# Wave_Fold_Osc_MAIN_V2_1.net
KiCad netlist of a schematic drawn in EAGLE
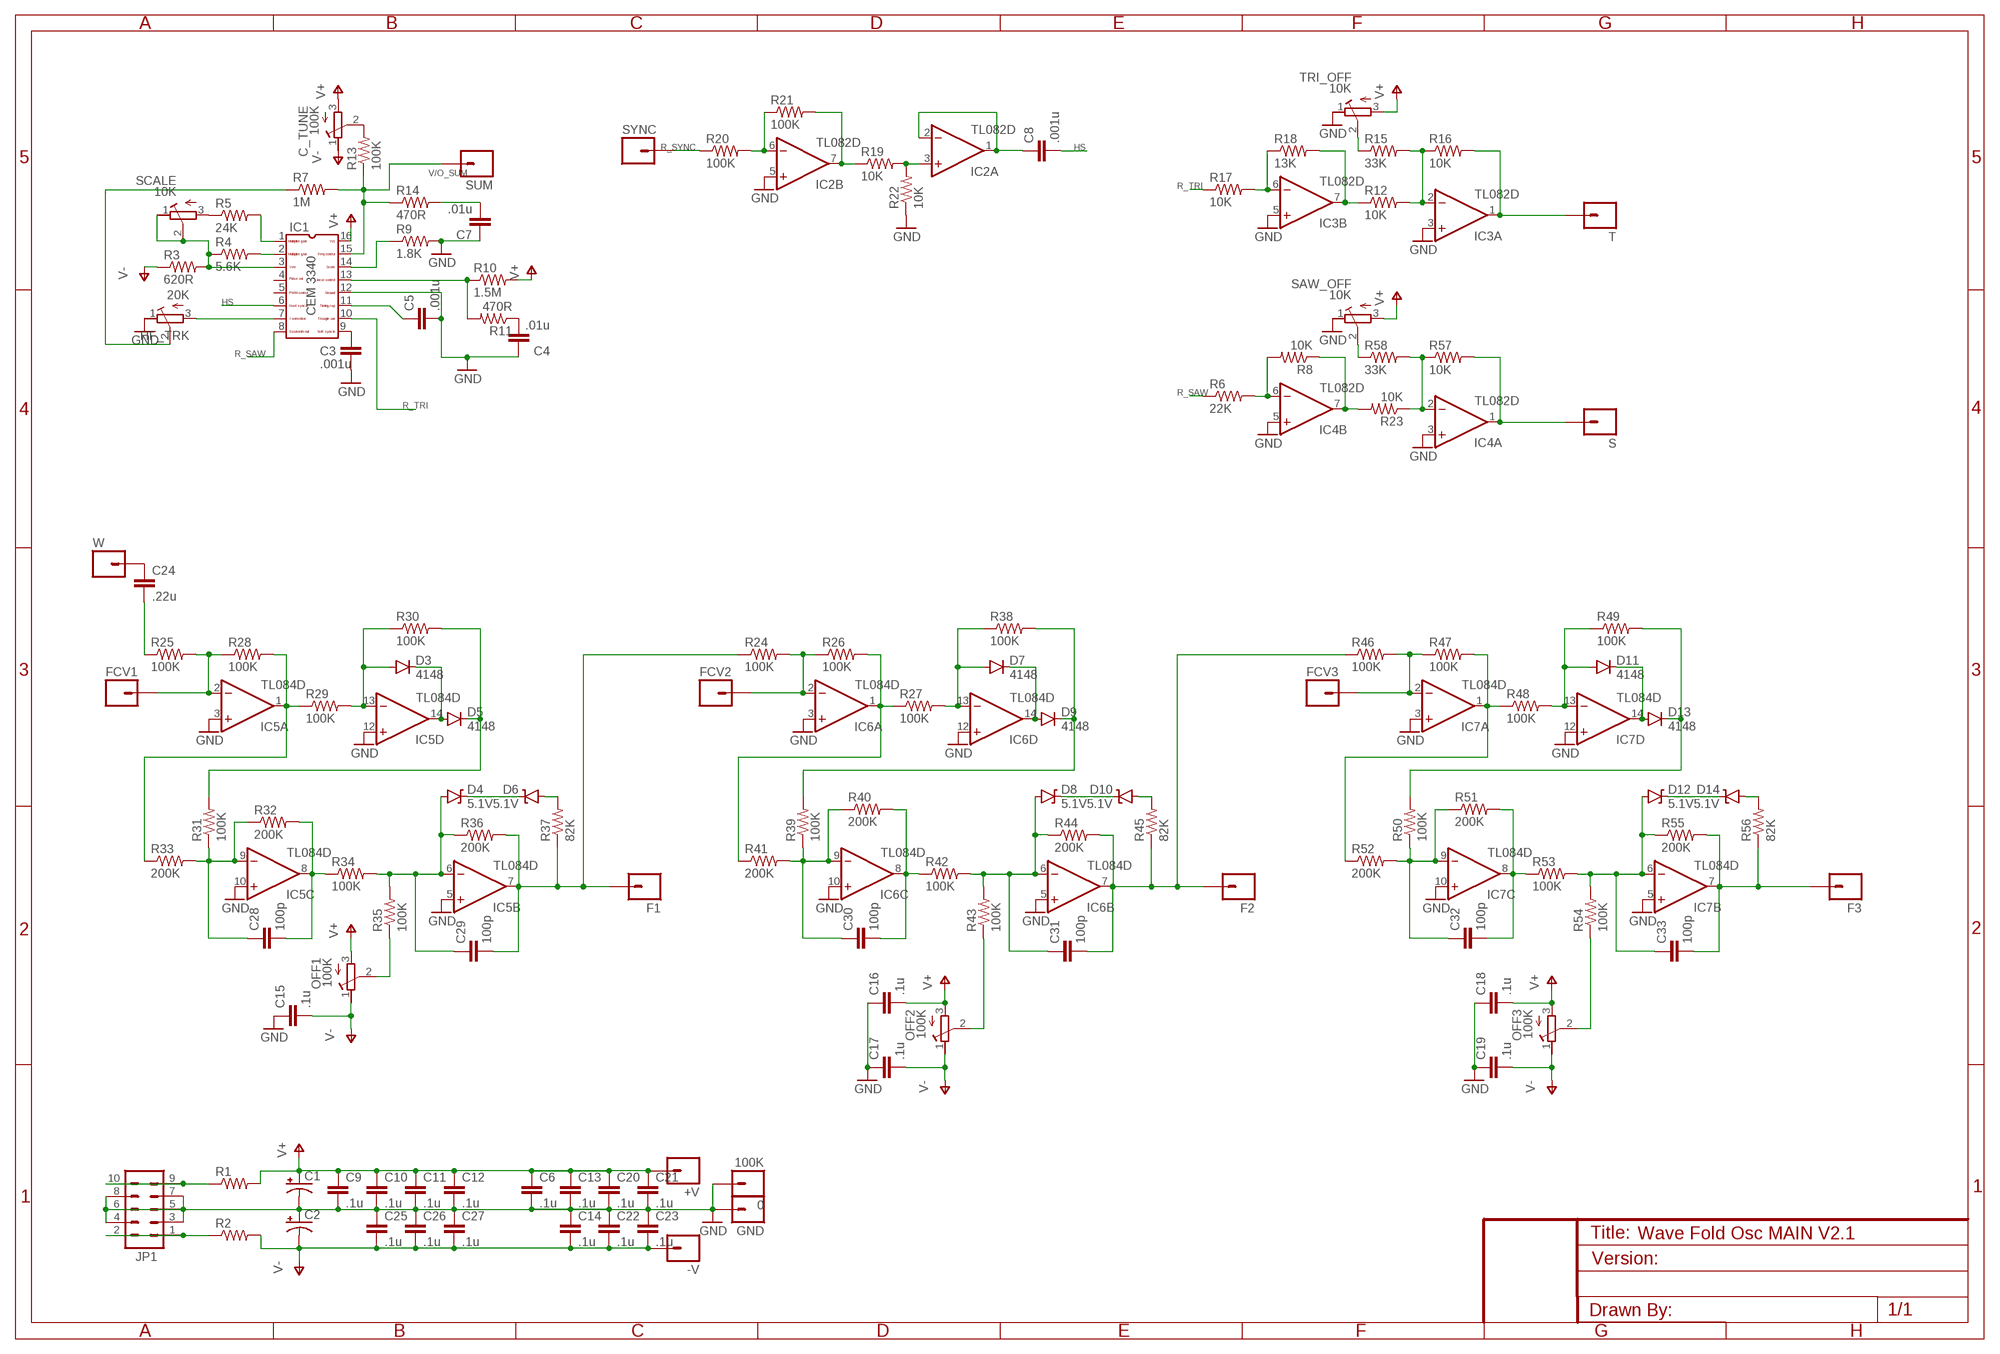
[diagram p0: schematic, sheet 1]

(export (version "E")
  (design (tool "Eeschema 10.0.6"))
  (components
    (comp (ref "+V")
      (value "M01PTH")
      (footprint "eagle-import:1X01")
      (libsource (lib "eagle-import") (part "M01PTH"))
    )
    (comp (ref "-V")
      (value "M01PTH")
      (footprint "eagle-import:1X01")
      (libsource (lib "eagle-import") (part "M01PTH"))
    )
    (comp (ref "0")
      (value "100K")
      (footprint "eagle-import:1X01")
      (libsource (lib "eagle-import") (part "M01PTH"))
    )
    (comp (ref "C1")
      (value "CAP_POLC")
      (footprint "eagle-import:PANASONIC_C")
      (libsource (lib "eagle-import") (part "CAP_POLC"))
    )
    (comp (ref "C2")
      (value "CAP_POLC")
      (footprint "eagle-import:PANASONIC_C")
      (libsource (lib "eagle-import") (part "CAP_POLC"))
    )
    (comp (ref "C3")
      (value ".001u")
      (footprint "eagle-import:0805")
      (libsource (lib "eagle-import") (part "CAP0805"))
    )
    (comp (ref "C4")
      (value ".01u")
      (footprint "eagle-import:0805")
      (libsource (lib "eagle-import") (part "CAP0805"))
    )
    (comp (ref "C5")
      (value ".001u")
      (footprint "eagle-import:C5B2.5")
      (libsource (lib "eagle-import") (part "C5/2.5"))
    )
    (comp (ref "C6")
      (value ".1u")
      (footprint "eagle-import:0805@1")
      (libsource (lib "eagle-import") (part "SparkFun-Passives_CAP0805"))
    )
    (comp (ref "C7")
      (value ".01u")
      (footprint "eagle-import:0805")
      (libsource (lib "eagle-import") (part "CAP0805"))
    )
    (comp (ref "C8")
      (value ".001u")
      (footprint "eagle-import:0805")
      (libsource (lib "eagle-import") (part "CAP0805"))
    )
    (comp (ref "C9")
      (value ".1u")
      (footprint "eagle-import:0805@1")
      (libsource (lib "eagle-import") (part "SparkFun-Passives_CAP0805"))
    )
    (comp (ref "C10")
      (value ".1u")
      (footprint "eagle-import:0805@1")
      (libsource (lib "eagle-import") (part "SparkFun-Passives_CAP0805"))
    )
    (comp (ref "C11")
      (value ".1u")
      (footprint "eagle-import:0805@1")
      (libsource (lib "eagle-import") (part "SparkFun-Passives_CAP0805"))
    )
    (comp (ref "C12")
      (value ".1u")
      (footprint "eagle-import:0805@1")
      (libsource (lib "eagle-import") (part "SparkFun-Passives_CAP0805"))
    )
    (comp (ref "C13")
      (value ".1u")
      (footprint "eagle-import:0805@1")
      (libsource (lib "eagle-import") (part "SparkFun-Passives_CAP0805"))
    )
    (comp (ref "C14")
      (value ".1u")
      (footprint "eagle-import:0805@1")
      (libsource (lib "eagle-import") (part "SparkFun-Passives_CAP0805"))
    )
    (comp (ref "C15")
      (value ".1u")
      (footprint "eagle-import:0805")
      (libsource (lib "eagle-import") (part "CAP0805"))
    )
    (comp (ref "C16")
      (value ".1u")
      (footprint "eagle-import:0805")
      (libsource (lib "eagle-import") (part "CAP0805"))
    )
    (comp (ref "C17")
      (value ".1u")
      (footprint "eagle-import:0805")
      (libsource (lib "eagle-import") (part "CAP0805"))
    )
    (comp (ref "C18")
      (value ".1u")
      (footprint "eagle-import:0805")
      (libsource (lib "eagle-import") (part "CAP0805"))
    )
    (comp (ref "C19")
      (value ".1u")
      (footprint "eagle-import:0805")
      (libsource (lib "eagle-import") (part "CAP0805"))
    )
    (comp (ref "C20")
      (value ".1u")
      (footprint "eagle-import:0805@1")
      (libsource (lib "eagle-import") (part "SparkFun-Passives_CAP0805"))
    )
    (comp (ref "C21")
      (value ".1u")
      (footprint "eagle-import:0805@1")
      (libsource (lib "eagle-import") (part "SparkFun-Passives_CAP0805"))
    )
    (comp (ref "C22")
      (value ".1u")
      (footprint "eagle-import:0805@1")
      (libsource (lib "eagle-import") (part "SparkFun-Passives_CAP0805"))
    )
    (comp (ref "C23")
      (value ".1u")
      (footprint "eagle-import:0805@1")
      (libsource (lib "eagle-import") (part "SparkFun-Passives_CAP0805"))
    )
    (comp (ref "C24")
      (value ".22u")
      (footprint "eagle-import:0805@1")
      (libsource (lib "eagle-import") (part "SparkFun-Passives_CAP0805"))
    )
    (comp (ref "C25")
      (value ".1u")
      (footprint "eagle-import:0805@1")
      (libsource (lib "eagle-import") (part "SparkFun-Passives_CAP0805"))
    )
    (comp (ref "C26")
      (value ".1u")
      (footprint "eagle-import:0805@1")
      (libsource (lib "eagle-import") (part "SparkFun-Passives_CAP0805"))
    )
    (comp (ref "C27")
      (value ".1u")
      (footprint "eagle-import:0805@1")
      (libsource (lib "eagle-import") (part "SparkFun-Passives_CAP0805"))
    )
    (comp (ref "C28")
      (value "100p")
      (footprint "eagle-import:0805@1")
      (libsource (lib "eagle-import") (part "SparkFun-Passives_CAP0805"))
    )
    (comp (ref "C29")
      (value "100p")
      (footprint "eagle-import:0805@1")
      (libsource (lib "eagle-import") (part "SparkFun-Passives_CAP0805"))
    )
    (comp (ref "C30")
      (value "100p")
      (footprint "eagle-import:0805@1")
      (libsource (lib "eagle-import") (part "SparkFun-Passives_CAP0805"))
    )
    (comp (ref "C31")
      (value "100p")
      (footprint "eagle-import:0805@1")
      (libsource (lib "eagle-import") (part "SparkFun-Passives_CAP0805"))
    )
    (comp (ref "C32")
      (value "100p")
      (footprint "eagle-import:0805@1")
      (libsource (lib "eagle-import") (part "SparkFun-Passives_CAP0805"))
    )
    (comp (ref "C33")
      (value "100p")
      (footprint "eagle-import:0805@1")
      (libsource (lib "eagle-import") (part "SparkFun-Passives_CAP0805"))
    )
    (comp (ref "C_TUNE")
      (value "100K")
      (footprint "eagle-import:RTRIM3314G")
      (libsource (lib "eagle-import") (part "R-TRIMM3314G"))
    )
    (comp (ref "D3")
      (value "4148")
      (footprint "eagle-import:SOD-123")
      (libsource (lib "eagle-import") (part "DIODESOD123"))
    )
    (comp (ref "D4")
      (value "5.1V")
      (footprint "eagle-import:SOD-123")
      (libsource (lib "eagle-import") (part "DIODE-ZENER16V"))
    )
    (comp (ref "D5")
      (value "4148")
      (footprint "eagle-import:SOD-123")
      (libsource (lib "eagle-import") (part "DIODESOD123"))
    )
    (comp (ref "D6")
      (value "5.1V")
      (footprint "eagle-import:SOD-123")
      (libsource (lib "eagle-import") (part "DIODE-ZENER16V"))
    )
    (comp (ref "D7")
      (value "4148")
      (footprint "eagle-import:SOD-123")
      (libsource (lib "eagle-import") (part "DIODESOD123"))
    )
    (comp (ref "D8")
      (value "5.1V")
      (footprint "eagle-import:SOD-123")
      (libsource (lib "eagle-import") (part "DIODE-ZENER16V"))
    )
    (comp (ref "D9")
      (value "4148")
      (footprint "eagle-import:SOD-123")
      (libsource (lib "eagle-import") (part "DIODESOD123"))
    )
    (comp (ref "D10")
      (value "5.1V")
      (footprint "eagle-import:SOD-123")
      (libsource (lib "eagle-import") (part "DIODE-ZENER16V"))
    )
    (comp (ref "D11")
      (value "4148")
      (footprint "eagle-import:SOD-123")
      (libsource (lib "eagle-import") (part "DIODESOD123"))
    )
    (comp (ref "D12")
      (value "5.1V")
      (footprint "eagle-import:SOD-123")
      (libsource (lib "eagle-import") (part "DIODE-ZENER16V"))
    )
    (comp (ref "D13")
      (value "4148")
      (footprint "eagle-import:SOD-123")
      (libsource (lib "eagle-import") (part "DIODESOD123"))
    )
    (comp (ref "D14")
      (value "5.1V")
      (footprint "eagle-import:SOD-123")
      (libsource (lib "eagle-import") (part "DIODE-ZENER16V"))
    )
    (comp (ref "F1")
      (value "M01PTH")
      (footprint "eagle-import:1X01")
      (libsource (lib "eagle-import") (part "M01PTH"))
    )
    (comp (ref "F2")
      (value "M01PTH")
      (footprint "eagle-import:1X01")
      (libsource (lib "eagle-import") (part "M01PTH"))
    )
    (comp (ref "F3")
      (value "M01PTH")
      (footprint "eagle-import:1X01")
      (libsource (lib "eagle-import") (part "M01PTH"))
    )
    (comp (ref "FCV1")
      (value "M01PTH")
      (footprint "eagle-import:1X01")
      (libsource (lib "eagle-import") (part "M01PTH"))
    )
    (comp (ref "FCV2")
      (value "M01PTH")
      (footprint "eagle-import:1X01")
      (libsource (lib "eagle-import") (part "M01PTH"))
    )
    (comp (ref "FCV3")
      (value "M01PTH")
      (footprint "eagle-import:1X01")
      (libsource (lib "eagle-import") (part "M01PTH"))
    )
    (comp (ref "GND")
      (value "M01PTH")
      (footprint "eagle-import:1X01")
      (libsource (lib "eagle-import") (part "M01PTH"))
    )
    (comp (ref "HF_TRK")
      (value "20K")
      (footprint "eagle-import:RTRIM3314G")
      (libsource (lib "eagle-import") (part "R-TRIMM3314G"))
    )
    (comp (ref "IC1")
      (value "CEM3340_SMD")
      (footprint "eagle-import:SO16")
      (libsource (lib "eagle-import") (part "CEM3340_SMD"))
    )
    (comp (ref "IC2")
      (value "TL082D")
      (footprint "eagle-import:SO08")
      (libsource (lib "eagle-import") (part "TL082D"))
    )
    (comp (ref "IC3")
      (value "TL082D")
      (footprint "eagle-import:SO08")
      (libsource (lib "eagle-import") (part "TL082D"))
    )
    (comp (ref "IC4")
      (value "TL082D")
      (footprint "eagle-import:SO08")
      (libsource (lib "eagle-import") (part "TL082D"))
    )
    (comp (ref "IC5")
      (value "TL084D")
      (footprint "eagle-import:SO14")
      (libsource (lib "eagle-import") (part "TL084D"))
    )
    (comp (ref "IC6")
      (value "TL084D")
      (footprint "eagle-import:SO14")
      (libsource (lib "eagle-import") (part "TL084D"))
    )
    (comp (ref "IC7")
      (value "TL084D")
      (footprint "eagle-import:SO14")
      (libsource (lib "eagle-import") (part "TL084D"))
    )
    (comp (ref "JP1")
      (value "M05X2PTH")
      (footprint "eagle-import:AVR_ICSP")
      (libsource (lib "eagle-import") (part "M05X2PTH"))
    )
    (comp (ref "OFF1")
      (value "100K")
      (footprint "eagle-import:RTRIM3314G")
      (libsource (lib "eagle-import") (part "R-TRIMM3314G"))
    )
    (comp (ref "OFF2")
      (value "100K")
      (footprint "eagle-import:RTRIM3314G")
      (libsource (lib "eagle-import") (part "R-TRIMM3314G"))
    )
    (comp (ref "OFF3")
      (value "100K")
      (footprint "eagle-import:RTRIM3314G")
      (libsource (lib "eagle-import") (part "R-TRIMM3314G"))
    )
    (comp (ref "R1")
      (value "RESISTOR0805-RES")
      (footprint "eagle-import:0805")
      (libsource (lib "eagle-import") (part "RESISTOR0805-RES"))
    )
    (comp (ref "R2")
      (value "RESISTOR0805-RES")
      (footprint "eagle-import:0805")
      (libsource (lib "eagle-import") (part "RESISTOR0805-RES"))
    )
    (comp (ref "R3")
      (value "620R")
      (footprint "eagle-import:0805")
      (libsource (lib "eagle-import") (part "RESISTOR0805-RES"))
    )
    (comp (ref "R4")
      (value "5.6K")
      (footprint "eagle-import:0805")
      (libsource (lib "eagle-import") (part "RESISTOR0805-RES"))
    )
    (comp (ref "R5")
      (value "24K")
      (footprint "eagle-import:0805")
      (libsource (lib "eagle-import") (part "RESISTOR0805-RES"))
    )
    (comp (ref "R6")
      (value "22K")
      (footprint "eagle-import:0805")
      (libsource (lib "eagle-import") (part "RESISTOR0805-RES"))
    )
    (comp (ref "R7")
      (value "1M")
      (footprint "eagle-import:0805")
      (libsource (lib "eagle-import") (part "RESISTOR0805-RES"))
    )
    (comp (ref "R8")
      (value "10K")
      (footprint "eagle-import:0805")
      (libsource (lib "eagle-import") (part "RESISTOR0805-RES"))
    )
    (comp (ref "R9")
      (value "1.8K")
      (footprint "eagle-import:0805")
      (libsource (lib "eagle-import") (part "RESISTOR0805-RES"))
    )
    (comp (ref "R10")
      (value "1.5M")
      (footprint "eagle-import:0805")
      (libsource (lib "eagle-import") (part "RESISTOR0805-RES"))
    )
    (comp (ref "R11")
      (value "470R")
      (footprint "eagle-import:0805")
      (libsource (lib "eagle-import") (part "RESISTOR0805-RES"))
    )
    (comp (ref "R12")
      (value "10K")
      (footprint "eagle-import:0805")
      (libsource (lib "eagle-import") (part "RESISTOR0805-RES"))
    )
    (comp (ref "R13")
      (value "100K")
      (footprint "eagle-import:0805")
      (libsource (lib "eagle-import") (part "RESISTOR0805-RES"))
    )
    (comp (ref "R14")
      (value "470R")
      (footprint "eagle-import:0805")
      (libsource (lib "eagle-import") (part "RESISTOR0805-RES"))
    )
    (comp (ref "R15")
      (value "33K")
      (footprint "eagle-import:0805")
      (libsource (lib "eagle-import") (part "RESISTOR0805-RES"))
    )
    (comp (ref "R16")
      (value "10K")
      (footprint "eagle-import:0805")
      (libsource (lib "eagle-import") (part "RESISTOR0805-RES"))
    )
    (comp (ref "R17")
      (value "10K")
      (footprint "eagle-import:0805")
      (libsource (lib "eagle-import") (part "RESISTOR0805-RES"))
    )
    (comp (ref "R18")
      (value "13K")
      (footprint "eagle-import:0805")
      (libsource (lib "eagle-import") (part "RESISTOR0805-RES"))
    )
    (comp (ref "R19")
      (value "10K")
      (footprint "eagle-import:0805")
      (libsource (lib "eagle-import") (part "RESISTOR0805-RES"))
    )
    (comp (ref "R20")
      (value "100K")
      (footprint "eagle-import:0805")
      (libsource (lib "eagle-import") (part "RESISTOR0805-RES"))
    )
    (comp (ref "R21")
      (value "100K")
      (footprint "eagle-import:0805")
      (libsource (lib "eagle-import") (part "RESISTOR0805-RES"))
    )
    (comp (ref "R22")
      (value "10K")
      (footprint "eagle-import:0805")
      (libsource (lib "eagle-import") (part "RESISTOR0805-RES"))
    )
    (comp (ref "R23")
      (value "10K")
      (footprint "eagle-import:0805")
      (libsource (lib "eagle-import") (part "RESISTOR0805-RES"))
    )
    (comp (ref "R24")
      (value "100K")
      (footprint "eagle-import:0805")
      (libsource (lib "eagle-import") (part "RESISTOR0805-RES"))
    )
    (comp (ref "R25")
      (value "100K")
      (footprint "eagle-import:0805")
      (libsource (lib "eagle-import") (part "RESISTOR0805-RES"))
    )
    (comp (ref "R26")
      (value "100K")
      (footprint "eagle-import:0805")
      (libsource (lib "eagle-import") (part "RESISTOR0805-RES"))
    )
    (comp (ref "R27")
      (value "100K")
      (footprint "eagle-import:0805")
      (libsource (lib "eagle-import") (part "RESISTOR0805-RES"))
    )
    (comp (ref "R28")
      (value "100K")
      (footprint "eagle-import:0805")
      (libsource (lib "eagle-import") (part "RESISTOR0805-RES"))
    )
    (comp (ref "R29")
      (value "100K")
      (footprint "eagle-import:0805")
      (libsource (lib "eagle-import") (part "RESISTOR0805-RES"))
    )
    (comp (ref "R30")
      (value "100K")
      (footprint "eagle-import:0805")
      (libsource (lib "eagle-import") (part "RESISTOR0805-RES"))
    )
    (comp (ref "R31")
      (value "100K")
      (footprint "eagle-import:0805")
      (libsource (lib "eagle-import") (part "RESISTOR0805-RES"))
    )
    (comp (ref "R32")
      (value "200K")
      (footprint "eagle-import:0805")
      (libsource (lib "eagle-import") (part "RESISTOR0805-RES"))
    )
    (comp (ref "R33")
      (value "200K")
      (footprint "eagle-import:0805")
      (libsource (lib "eagle-import") (part "RESISTOR0805-RES"))
    )
    (comp (ref "R34")
      (value "100K")
      (footprint "eagle-import:0805")
      (libsource (lib "eagle-import") (part "RESISTOR0805-RES"))
    )
    (comp (ref "R35")
      (value "100K")
      (footprint "eagle-import:0805")
      (libsource (lib "eagle-import") (part "RESISTOR0805-RES"))
    )
    (comp (ref "R36")
      (value "200K")
      (footprint "eagle-import:0805")
      (libsource (lib "eagle-import") (part "RESISTOR0805-RES"))
    )
    (comp (ref "R37")
      (value "82K")
      (footprint "eagle-import:0805")
      (libsource (lib "eagle-import") (part "RESISTOR0805-RES"))
    )
    (comp (ref "R38")
      (value "100K")
      (footprint "eagle-import:0805")
      (libsource (lib "eagle-import") (part "RESISTOR0805-RES"))
    )
    (comp (ref "R39")
      (value "100K")
      (footprint "eagle-import:0805")
      (libsource (lib "eagle-import") (part "RESISTOR0805-RES"))
    )
    (comp (ref "R40")
      (value "200K")
      (footprint "eagle-import:0805")
      (libsource (lib "eagle-import") (part "RESISTOR0805-RES"))
    )
    (comp (ref "R41")
      (value "200K")
      (footprint "eagle-import:0805")
      (libsource (lib "eagle-import") (part "RESISTOR0805-RES"))
    )
    (comp (ref "R42")
      (value "100K")
      (footprint "eagle-import:0805")
      (libsource (lib "eagle-import") (part "RESISTOR0805-RES"))
    )
    (comp (ref "R43")
      (value "100K")
      (footprint "eagle-import:0805")
      (libsource (lib "eagle-import") (part "RESISTOR0805-RES"))
    )
    (comp (ref "R44")
      (value "200K")
      (footprint "eagle-import:0805")
      (libsource (lib "eagle-import") (part "RESISTOR0805-RES"))
    )
    (comp (ref "R45")
      (value "82K")
      (footprint "eagle-import:0805")
      (libsource (lib "eagle-import") (part "RESISTOR0805-RES"))
    )
    (comp (ref "R46")
      (value "100K")
      (footprint "eagle-import:0805")
      (libsource (lib "eagle-import") (part "RESISTOR0805-RES"))
    )
    (comp (ref "R47")
      (value "100K")
      (footprint "eagle-import:0805")
      (libsource (lib "eagle-import") (part "RESISTOR0805-RES"))
    )
    (comp (ref "R48")
      (value "100K")
      (footprint "eagle-import:0805")
      (libsource (lib "eagle-import") (part "RESISTOR0805-RES"))
    )
    (comp (ref "R49")
      (value "100K")
      (footprint "eagle-import:0805")
      (libsource (lib "eagle-import") (part "RESISTOR0805-RES"))
    )
    (comp (ref "R50")
      (value "100K")
      (footprint "eagle-import:0805")
      (libsource (lib "eagle-import") (part "RESISTOR0805-RES"))
    )
    (comp (ref "R51")
      (value "200K")
      (footprint "eagle-import:0805")
      (libsource (lib "eagle-import") (part "RESISTOR0805-RES"))
    )
    (comp (ref "R52")
      (value "200K")
      (footprint "eagle-import:0805")
      (libsource (lib "eagle-import") (part "RESISTOR0805-RES"))
    )
    (comp (ref "R53")
      (value "100K")
      (footprint "eagle-import:0805")
      (libsource (lib "eagle-import") (part "RESISTOR0805-RES"))
    )
    (comp (ref "R54")
      (value "100K")
      (footprint "eagle-import:0805")
      (libsource (lib "eagle-import") (part "RESISTOR0805-RES"))
    )
    (comp (ref "R55")
      (value "200K")
      (footprint "eagle-import:0805")
      (libsource (lib "eagle-import") (part "RESISTOR0805-RES"))
    )
    (comp (ref "R56")
      (value "82K")
      (footprint "eagle-import:0805")
      (libsource (lib "eagle-import") (part "RESISTOR0805-RES"))
    )
    (comp (ref "R57")
      (value "10K")
      (footprint "eagle-import:0805")
      (libsource (lib "eagle-import") (part "RESISTOR0805-RES"))
    )
    (comp (ref "R58")
      (value "33K")
      (footprint "eagle-import:0805")
      (libsource (lib "eagle-import") (part "RESISTOR0805-RES"))
    )
    (comp (ref "S")
      (value "M01PTH")
      (footprint "eagle-import:1X01")
      (libsource (lib "eagle-import") (part "M01PTH"))
    )
    (comp (ref "SAW_OFF")
      (value "10K")
      (footprint "eagle-import:RTRIM3314G")
      (libsource (lib "eagle-import") (part "R-TRIMM3314G"))
    )
    (comp (ref "SCALE")
      (value "10K")
      (footprint "eagle-import:RTRIM3314G")
      (libsource (lib "eagle-import") (part "R-TRIMM3314G"))
    )
    (comp (ref "SUM")
      (value "M01PTH")
      (footprint "eagle-import:1X01")
      (libsource (lib "eagle-import") (part "M01PTH"))
    )
    (comp (ref "SYNC")
      (value "M01PTH")
      (footprint "eagle-import:1X01")
      (libsource (lib "eagle-import") (part "M01PTH"))
    )
    (comp (ref "T")
      (value "M01PTH")
      (footprint "eagle-import:1X01")
      (libsource (lib "eagle-import") (part "M01PTH"))
    )
    (comp (ref "TRI_OFF")
      (value "10K")
      (footprint "eagle-import:RTRIM3314G")
      (libsource (lib "eagle-import") (part "R-TRIMM3314G"))
    )
    (comp (ref "W")
      (value "M01PTH")
      (footprint "eagle-import:1X01")
      (libsource (lib "eagle-import") (part "M01PTH"))
    )
  )
  (nets
    (net (code "1") (name "/HS") (class "Default")
      (node (ref "C8") (pin "2") (pinfunction "2_2") (pintype "passive"))
      (node (ref "IC1") (pin "6") (pinfunction "6_6") (pintype "input"))
    )
    (net (code "2") (name "/R_SAW") (class "Default")
      (node (ref "IC1") (pin "8") (pinfunction "8_8") (pintype "output"))
      (node (ref "R6") (pin "1") (pinfunction "1_1") (pintype "passive"))
    )
    (net (code "3") (name "/R_SYNC") (class "Default")
      (node (ref "R20") (pin "1") (pinfunction "1_1") (pintype "passive"))
      (node (ref "SYNC") (pin "1") (pinfunction "1_1") (pintype "passive"))
    )
    (net (code "4") (name "/R_TRI") (class "Default")
      (node (ref "IC1") (pin "10") (pinfunction "10_10") (pintype "output"))
      (node (ref "R17") (pin "1") (pinfunction "1_1") (pintype "passive"))
    )
    (net (code "5") (name "/V{slash}O_SUM") (class "Default")
      (node (ref "IC1") (pin "15") (pinfunction "15_15") (pintype "input"))
      (node (ref "R13") (pin "1") (pinfunction "1_1") (pintype "passive"))
      (node (ref "R14") (pin "1") (pinfunction "1_1") (pintype "passive"))
      (node (ref "R7") (pin "2") (pinfunction "2_2") (pintype "passive"))
      (node (ref "SUM") (pin "1") (pinfunction "1_1") (pintype "passive"))
    )
    (net (code "6") (name "GND") (class "Default")
      (node (ref "0") (pin "1") (pinfunction "1_1") (pintype "passive"))
      (node (ref "C1") (pin "-") (pinfunction "-_-") (pintype "passive"))
      (node (ref "C10") (pin "2") (pinfunction "2_2") (pintype "passive"))
      (node (ref "C11") (pin "2") (pinfunction "2_2") (pintype "passive"))
      (node (ref "C12") (pin "2") (pinfunction "2_2") (pintype "passive"))
      (node (ref "C13") (pin "2") (pinfunction "2_2") (pintype "passive"))
      (node (ref "C14") (pin "1") (pinfunction "1_1") (pintype "passive"))
      (node (ref "C15") (pin "1") (pinfunction "1_1") (pintype "passive"))
      (node (ref "C16") (pin "1") (pinfunction "1_1") (pintype "passive"))
      (node (ref "C17") (pin "1") (pinfunction "1_1") (pintype "passive"))
      (node (ref "C18") (pin "1") (pinfunction "1_1") (pintype "passive"))
      (node (ref "C19") (pin "1") (pinfunction "1_1") (pintype "passive"))
      (node (ref "C2") (pin "+") (pinfunction "+_+") (pintype "passive"))
      (node (ref "C20") (pin "2") (pinfunction "2_2") (pintype "passive"))
      (node (ref "C21") (pin "2") (pinfunction "2_2") (pintype "passive"))
      (node (ref "C22") (pin "1") (pinfunction "1_1") (pintype "passive"))
      (node (ref "C23") (pin "1") (pinfunction "1_1") (pintype "passive"))
      (node (ref "C25") (pin "1") (pinfunction "1_1") (pintype "passive"))
      (node (ref "C26") (pin "1") (pinfunction "1_1") (pintype "passive"))
      (node (ref "C27") (pin "1") (pinfunction "1_1") (pintype "passive"))
      (node (ref "C3") (pin "2") (pinfunction "2_2") (pintype "passive"))
      (node (ref "C4") (pin "1") (pinfunction "1_1") (pintype "passive"))
      (node (ref "C5") (pin "2") (pinfunction "2_2") (pintype "passive"))
      (node (ref "C6") (pin "2") (pinfunction "2_2") (pintype "passive"))
      (node (ref "C7") (pin "1") (pinfunction "1_1") (pintype "passive"))
      (node (ref "C9") (pin "2") (pinfunction "2_2") (pintype "passive"))
      (node (ref "GND") (pin "1") (pinfunction "1_1") (pintype "passive"))
      (node (ref "HF_TRK") (pin "1") (pinfunction "E_1") (pintype "passive"))
      (node (ref "IC1") (pin "12") (pinfunction "12_12") (pintype "power_in"))
      (node (ref "IC2") (pin "5") (pinfunction "+IN_5") (pintype "input"))
      (node (ref "IC3") (pin "3") (pinfunction "+IN_3") (pintype "input"))
      (node (ref "IC3") (pin "5") (pinfunction "+IN_5") (pintype "input"))
      (node (ref "IC4") (pin "3") (pinfunction "+IN_3") (pintype "input"))
      (node (ref "IC4") (pin "5") (pinfunction "+IN_5") (pintype "input"))
      (node (ref "IC5") (pin "10") (pinfunction "+IN_10") (pintype "input"))
      (node (ref "IC5") (pin "12") (pinfunction "+IN_12") (pintype "input"))
      (node (ref "IC5") (pin "3") (pinfunction "+IN_3") (pintype "input"))
      (node (ref "IC5") (pin "5") (pinfunction "+IN_5") (pintype "input"))
      (node (ref "IC6") (pin "10") (pinfunction "+IN_10") (pintype "input"))
      (node (ref "IC6") (pin "12") (pinfunction "+IN_12") (pintype "input"))
      (node (ref "IC6") (pin "3") (pinfunction "+IN_3") (pintype "input"))
      (node (ref "IC6") (pin "5") (pinfunction "+IN_5") (pintype "input"))
      (node (ref "IC7") (pin "10") (pinfunction "+IN_10") (pintype "input"))
      (node (ref "IC7") (pin "12") (pinfunction "+IN_12") (pintype "input"))
      (node (ref "IC7") (pin "3") (pinfunction "+IN_3") (pintype "input"))
      (node (ref "IC7") (pin "5") (pinfunction "+IN_5") (pintype "input"))
      (node (ref "JP1") (pin "3") (pinfunction "3_3") (pintype "passive"))
      (node (ref "JP1") (pin "4") (pinfunction "4_4") (pintype "passive"))
      (node (ref "JP1") (pin "5") (pinfunction "5_5") (pintype "passive"))
      (node (ref "JP1") (pin "6") (pinfunction "6_6") (pintype "passive"))
      (node (ref "JP1") (pin "7") (pinfunction "7_7") (pintype "passive"))
      (node (ref "JP1") (pin "8") (pinfunction "8_8") (pintype "passive"))
      (node (ref "R22") (pin "1") (pinfunction "1_1") (pintype "passive"))
      (node (ref "R9") (pin "2") (pinfunction "2_2") (pintype "passive"))
      (node (ref "SAW_OFF") (pin "1") (pinfunction "E_1") (pintype "passive"))
      (node (ref "TRI_OFF") (pin "1") (pinfunction "E_1") (pintype "passive"))
    )
    (net (code "7") (name "Net-(C3-Pad1)") (class "Default")
      (node (ref "C3") (pin "1") (pinfunction "1_1") (pintype "passive"))
      (node (ref "IC1") (pin "9") (pinfunction "9_9") (pintype "input"))
    )
    (net (code "8") (name "Net-(C4-Pad2)") (class "Default")
      (node (ref "C4") (pin "2") (pinfunction "2_2") (pintype "passive"))
      (node (ref "R11") (pin "1") (pinfunction "1_1") (pintype "passive"))
    )
    (net (code "9") (name "Net-(C5-Pad1)") (class "Default")
      (node (ref "C5") (pin "1") (pinfunction "1_1") (pintype "passive"))
      (node (ref "IC1") (pin "11") (pinfunction "11_11") (pintype "bidirectional"))
    )
    (net (code "10") (name "Net-(C7-Pad2)") (class "Default")
      (node (ref "C7") (pin "2") (pinfunction "2_2") (pintype "passive"))
      (node (ref "R14") (pin "2") (pinfunction "2_2") (pintype "passive"))
    )
    (net (code "11") (name "Net-(C24-Pad1)") (class "Default")
      (node (ref "C24") (pin "1") (pinfunction "1_1") (pintype "passive"))
      (node (ref "W") (pin "1") (pinfunction "1_1") (pintype "passive"))
    )
    (net (code "12") (name "Net-(C24-Pad2)") (class "Default")
      (node (ref "C24") (pin "2") (pinfunction "2_2") (pintype "passive"))
      (node (ref "R25") (pin "1") (pinfunction "1_1") (pintype "passive"))
    )
    (net (code "13") (name "Net-(C_TUNE-S)") (class "Default")
      (node (ref "C_TUNE") (pin "2") (pinfunction "S_2") (pintype "passive"))
      (node (ref "R13") (pin "2") (pinfunction "2_2") (pintype "passive"))
    )
    (net (code "14") (name "Net-(D4-PadC)") (class "Default")
      (node (ref "D4") (pin "C") (pinfunction "C_C") (pintype "passive"))
      (node (ref "D6") (pin "C") (pinfunction "C_C") (pintype "passive"))
    )
    (net (code "15") (name "Net-(D5-PadC)") (class "Default")
      (node (ref "D5") (pin "C") (pinfunction "C_C") (pintype "passive"))
      (node (ref "R30") (pin "2") (pinfunction "2_2") (pintype "passive"))
      (node (ref "R31") (pin "2") (pinfunction "2_2") (pintype "passive"))
    )
    (net (code "16") (name "Net-(D6-PadA)") (class "Default")
      (node (ref "D6") (pin "A") (pinfunction "A_A") (pintype "passive"))
      (node (ref "R37") (pin "2") (pinfunction "2_2") (pintype "passive"))
    )
    (net (code "17") (name "Net-(D9-PadC)") (class "Default")
      (node (ref "D9") (pin "C") (pinfunction "C_C") (pintype "passive"))
      (node (ref "R38") (pin "2") (pinfunction "2_2") (pintype "passive"))
      (node (ref "R39") (pin "2") (pinfunction "2_2") (pintype "passive"))
    )
    (net (code "18") (name "Net-(D10-PadA)") (class "Default")
      (node (ref "D10") (pin "A") (pinfunction "A_A") (pintype "passive"))
      (node (ref "R45") (pin "2") (pinfunction "2_2") (pintype "passive"))
    )
    (net (code "19") (name "Net-(D10-PadC)") (class "Default")
      (node (ref "D10") (pin "C") (pinfunction "C_C") (pintype "passive"))
      (node (ref "D8") (pin "C") (pinfunction "C_C") (pintype "passive"))
    )
    (net (code "20") (name "Net-(D12-PadC)") (class "Default")
      (node (ref "D12") (pin "C") (pinfunction "C_C") (pintype "passive"))
      (node (ref "D14") (pin "C") (pinfunction "C_C") (pintype "passive"))
    )
    (net (code "21") (name "Net-(D13-PadC)") (class "Default")
      (node (ref "D13") (pin "C") (pinfunction "C_C") (pintype "passive"))
      (node (ref "R49") (pin "2") (pinfunction "2_2") (pintype "passive"))
      (node (ref "R50") (pin "2") (pinfunction "2_2") (pintype "passive"))
    )
    (net (code "22") (name "Net-(D14-PadA)") (class "Default")
      (node (ref "D14") (pin "A") (pinfunction "A_A") (pintype "passive"))
      (node (ref "R56") (pin "2") (pinfunction "2_2") (pintype "passive"))
    )
    (net (code "23") (name "Net-(HF_TRK-A)") (class "Default")
      (node (ref "HF_TRK") (pin "3") (pinfunction "A_3") (pintype "passive"))
      (node (ref "IC1") (pin "7") (pinfunction "7_7") (pintype "bidirectional"))
    )
    (net (code "24") (name "Net-(HF_TRK-S)") (class "Default")
      (node (ref "HF_TRK") (pin "2") (pinfunction "S_2") (pintype "passive"))
      (node (ref "R7") (pin "1") (pinfunction "1_1") (pintype "passive"))
    )
    (net (code "25") (name "Net-(IC1-Pad1)") (class "Default")
      (node (ref "IC1") (pin "1") (pinfunction "1_1") (pintype "bidirectional"))
      (node (ref "R5") (pin "2") (pinfunction "2_2") (pintype "passive"))
    )
    (net (code "26") (name "Net-(IC1-Pad2)") (class "Default")
      (node (ref "IC1") (pin "2") (pinfunction "2_2") (pintype "bidirectional"))
      (node (ref "R4") (pin "2") (pinfunction "2_2") (pintype "passive"))
    )
    (net (code "27") (name "Net-(IC1-Pad13)") (class "Default")
      (node (ref "IC1") (pin "13") (pinfunction "13_13") (pintype "input"))
      (node (ref "R10") (pin "1") (pinfunction "1_1") (pintype "passive"))
      (node (ref "R11") (pin "2") (pinfunction "2_2") (pintype "passive"))
    )
    (net (code "28") (name "Net-(IC1-Pad14)") (class "Default")
      (node (ref "IC1") (pin "14") (pinfunction "14_14") (pintype "input"))
      (node (ref "R9") (pin "1") (pinfunction "1_1") (pintype "passive"))
    )
    (net (code "29") (name "Net-(IC2A-+IN)") (class "Default")
      (node (ref "IC2") (pin "3") (pinfunction "+IN_3") (pintype "input"))
      (node (ref "R19") (pin "2") (pinfunction "2_2") (pintype "passive"))
      (node (ref "R22") (pin "2") (pinfunction "2_2") (pintype "passive"))
    )
    (net (code "30") (name "Net-(IC2A--IN)") (class "Default")
      (node (ref "C8") (pin "1") (pinfunction "1_1") (pintype "passive"))
      (node (ref "IC2") (pin "1") (pinfunction "OUT_1") (pintype "output"))
      (node (ref "IC2") (pin "2") (pinfunction "-IN_2") (pintype "input"))
    )
    (net (code "31") (name "Net-(IC2B--IN)") (class "Default")
      (node (ref "IC2") (pin "6") (pinfunction "-IN_6") (pintype "input"))
      (node (ref "R20") (pin "2") (pinfunction "2_2") (pintype "passive"))
      (node (ref "R21") (pin "1") (pinfunction "1_1") (pintype "passive"))
    )
    (net (code "32") (name "Net-(IC2B-OUT)") (class "Default")
      (node (ref "IC2") (pin "7") (pinfunction "OUT_7") (pintype "output"))
      (node (ref "R19") (pin "1") (pinfunction "1_1") (pintype "passive"))
      (node (ref "R21") (pin "2") (pinfunction "2_2") (pintype "passive"))
    )
    (net (code "33") (name "Net-(IC3A--IN)") (class "Default")
      (node (ref "IC3") (pin "2") (pinfunction "-IN_2") (pintype "input"))
      (node (ref "R12") (pin "2") (pinfunction "2_2") (pintype "passive"))
      (node (ref "R15") (pin "2") (pinfunction "2_2") (pintype "passive"))
      (node (ref "R16") (pin "1") (pinfunction "1_1") (pintype "passive"))
    )
    (net (code "34") (name "Net-(IC3A-OUT)") (class "Default")
      (node (ref "IC3") (pin "1") (pinfunction "OUT_1") (pintype "output"))
      (node (ref "R16") (pin "2") (pinfunction "2_2") (pintype "passive"))
      (node (ref "T") (pin "1") (pinfunction "1_1") (pintype "passive"))
    )
    (net (code "35") (name "Net-(IC3B--IN)") (class "Default")
      (node (ref "IC3") (pin "6") (pinfunction "-IN_6") (pintype "input"))
      (node (ref "R17") (pin "2") (pinfunction "2_2") (pintype "passive"))
      (node (ref "R18") (pin "1") (pinfunction "1_1") (pintype "passive"))
    )
    (net (code "36") (name "Net-(IC3B-OUT)") (class "Default")
      (node (ref "IC3") (pin "7") (pinfunction "OUT_7") (pintype "output"))
      (node (ref "R12") (pin "1") (pinfunction "1_1") (pintype "passive"))
      (node (ref "R18") (pin "2") (pinfunction "2_2") (pintype "passive"))
    )
    (net (code "37") (name "Net-(IC4A--IN)") (class "Default")
      (node (ref "IC4") (pin "2") (pinfunction "-IN_2") (pintype "input"))
      (node (ref "R23") (pin "1") (pinfunction "1_1") (pintype "passive"))
      (node (ref "R57") (pin "1") (pinfunction "1_1") (pintype "passive"))
      (node (ref "R58") (pin "2") (pinfunction "2_2") (pintype "passive"))
    )
    (net (code "38") (name "Net-(IC4A-OUT)") (class "Default")
      (node (ref "IC4") (pin "1") (pinfunction "OUT_1") (pintype "output"))
      (node (ref "R57") (pin "2") (pinfunction "2_2") (pintype "passive"))
      (node (ref "S") (pin "1") (pinfunction "1_1") (pintype "passive"))
    )
    (net (code "39") (name "Net-(IC4B--IN)") (class "Default")
      (node (ref "IC4") (pin "6") (pinfunction "-IN_6") (pintype "input"))
      (node (ref "R6") (pin "2") (pinfunction "2_2") (pintype "passive"))
      (node (ref "R8") (pin "2") (pinfunction "2_2") (pintype "passive"))
    )
    (net (code "40") (name "Net-(IC4B-OUT)") (class "Default")
      (node (ref "IC4") (pin "7") (pinfunction "OUT_7") (pintype "output"))
      (node (ref "R23") (pin "2") (pinfunction "2_2") (pintype "passive"))
      (node (ref "R8") (pin "1") (pinfunction "1_1") (pintype "passive"))
    )
    (net (code "41") (name "Net-(IC5A--IN)") (class "Default")
      (node (ref "FCV1") (pin "1") (pinfunction "1_1") (pintype "passive"))
      (node (ref "IC5") (pin "2") (pinfunction "-IN_2") (pintype "input"))
      (node (ref "R25") (pin "2") (pinfunction "2_2") (pintype "passive"))
      (node (ref "R28") (pin "1") (pinfunction "1_1") (pintype "passive"))
    )
    (net (code "42") (name "Net-(IC5A-OUT)") (class "Default")
      (node (ref "IC5") (pin "1") (pinfunction "OUT_1") (pintype "output"))
      (node (ref "R28") (pin "2") (pinfunction "2_2") (pintype "passive"))
      (node (ref "R29") (pin "1") (pinfunction "1_1") (pintype "passive"))
      (node (ref "R33") (pin "1") (pinfunction "1_1") (pintype "passive"))
    )
    (net (code "43") (name "Net-(IC5B--IN)") (class "Default")
      (node (ref "C29") (pin "1") (pinfunction "1_1") (pintype "passive"))
      (node (ref "D4") (pin "A") (pinfunction "A_A") (pintype "passive"))
      (node (ref "IC5") (pin "6") (pinfunction "-IN_6") (pintype "input"))
      (node (ref "R34") (pin "2") (pinfunction "2_2") (pintype "passive"))
      (node (ref "R35") (pin "2") (pinfunction "2_2") (pintype "passive"))
      (node (ref "R36") (pin "1") (pinfunction "1_1") (pintype "passive"))
    )
    (net (code "44") (name "Net-(IC5B-OUT)") (class "Default")
      (node (ref "C29") (pin "2") (pinfunction "2_2") (pintype "passive"))
      (node (ref "F1") (pin "1") (pinfunction "1_1") (pintype "passive"))
      (node (ref "IC5") (pin "7") (pinfunction "OUT_7") (pintype "output"))
      (node (ref "R24") (pin "1") (pinfunction "1_1") (pintype "passive"))
      (node (ref "R36") (pin "2") (pinfunction "2_2") (pintype "passive"))
      (node (ref "R37") (pin "1") (pinfunction "1_1") (pintype "passive"))
    )
    (net (code "45") (name "Net-(IC5C--IN)") (class "Default")
      (node (ref "C28") (pin "1") (pinfunction "1_1") (pintype "passive"))
      (node (ref "IC5") (pin "9") (pinfunction "-IN_9") (pintype "input"))
      (node (ref "R31") (pin "1") (pinfunction "1_1") (pintype "passive"))
      (node (ref "R32") (pin "1") (pinfunction "1_1") (pintype "passive"))
      (node (ref "R33") (pin "2") (pinfunction "2_2") (pintype "passive"))
    )
    (net (code "46") (name "Net-(IC5C-OUT)") (class "Default")
      (node (ref "C28") (pin "2") (pinfunction "2_2") (pintype "passive"))
      (node (ref "IC5") (pin "8") (pinfunction "OUT_8") (pintype "output"))
      (node (ref "R32") (pin "2") (pinfunction "2_2") (pintype "passive"))
      (node (ref "R34") (pin "1") (pinfunction "1_1") (pintype "passive"))
    )
    (net (code "47") (name "Net-(IC5D--IN)") (class "Default")
      (node (ref "D3") (pin "A") (pinfunction "A_A") (pintype "passive"))
      (node (ref "IC5") (pin "13") (pinfunction "-IN_13") (pintype "input"))
      (node (ref "R29") (pin "2") (pinfunction "2_2") (pintype "passive"))
      (node (ref "R30") (pin "1") (pinfunction "1_1") (pintype "passive"))
    )
    (net (code "48") (name "Net-(IC5D-OUT)") (class "Default")
      (node (ref "D3") (pin "C") (pinfunction "C_C") (pintype "passive"))
      (node (ref "D5") (pin "A") (pinfunction "A_A") (pintype "passive"))
      (node (ref "IC5") (pin "14") (pinfunction "OUT_14") (pintype "output"))
    )
    (net (code "49") (name "Net-(IC6A--IN)") (class "Default")
      (node (ref "FCV2") (pin "1") (pinfunction "1_1") (pintype "passive"))
      (node (ref "IC6") (pin "2") (pinfunction "-IN_2") (pintype "input"))
      (node (ref "R24") (pin "2") (pinfunction "2_2") (pintype "passive"))
      (node (ref "R26") (pin "1") (pinfunction "1_1") (pintype "passive"))
    )
    (net (code "50") (name "Net-(IC6A-OUT)") (class "Default")
      (node (ref "IC6") (pin "1") (pinfunction "OUT_1") (pintype "output"))
      (node (ref "R26") (pin "2") (pinfunction "2_2") (pintype "passive"))
      (node (ref "R27") (pin "1") (pinfunction "1_1") (pintype "passive"))
      (node (ref "R41") (pin "1") (pinfunction "1_1") (pintype "passive"))
    )
    (net (code "51") (name "Net-(IC6B--IN)") (class "Default")
      (node (ref "C31") (pin "1") (pinfunction "1_1") (pintype "passive"))
      (node (ref "D8") (pin "A") (pinfunction "A_A") (pintype "passive"))
      (node (ref "IC6") (pin "6") (pinfunction "-IN_6") (pintype "input"))
      (node (ref "R42") (pin "2") (pinfunction "2_2") (pintype "passive"))
      (node (ref "R43") (pin "2") (pinfunction "2_2") (pintype "passive"))
      (node (ref "R44") (pin "1") (pinfunction "1_1") (pintype "passive"))
    )
    (net (code "52") (name "Net-(IC6B-OUT)") (class "Default")
      (node (ref "C31") (pin "2") (pinfunction "2_2") (pintype "passive"))
      (node (ref "F2") (pin "1") (pinfunction "1_1") (pintype "passive"))
      (node (ref "IC6") (pin "7") (pinfunction "OUT_7") (pintype "output"))
      (node (ref "R44") (pin "2") (pinfunction "2_2") (pintype "passive"))
      (node (ref "R45") (pin "1") (pinfunction "1_1") (pintype "passive"))
      (node (ref "R46") (pin "1") (pinfunction "1_1") (pintype "passive"))
    )
    (net (code "53") (name "Net-(IC6C--IN)") (class "Default")
      (node (ref "C30") (pin "1") (pinfunction "1_1") (pintype "passive"))
      (node (ref "IC6") (pin "9") (pinfunction "-IN_9") (pintype "input"))
      (node (ref "R39") (pin "1") (pinfunction "1_1") (pintype "passive"))
      (node (ref "R40") (pin "1") (pinfunction "1_1") (pintype "passive"))
      (node (ref "R41") (pin "2") (pinfunction "2_2") (pintype "passive"))
    )
    (net (code "54") (name "Net-(IC6C-OUT)") (class "Default")
      (node (ref "C30") (pin "2") (pinfunction "2_2") (pintype "passive"))
      (node (ref "IC6") (pin "8") (pinfunction "OUT_8") (pintype "output"))
      (node (ref "R40") (pin "2") (pinfunction "2_2") (pintype "passive"))
      (node (ref "R42") (pin "1") (pinfunction "1_1") (pintype "passive"))
    )
    (net (code "55") (name "Net-(IC6D--IN)") (class "Default")
      (node (ref "D7") (pin "A") (pinfunction "A_A") (pintype "passive"))
      (node (ref "IC6") (pin "13") (pinfunction "-IN_13") (pintype "input"))
      (node (ref "R27") (pin "2") (pinfunction "2_2") (pintype "passive"))
      (node (ref "R38") (pin "1") (pinfunction "1_1") (pintype "passive"))
    )
    (net (code "56") (name "Net-(IC6D-OUT)") (class "Default")
      (node (ref "D7") (pin "C") (pinfunction "C_C") (pintype "passive"))
      (node (ref "D9") (pin "A") (pinfunction "A_A") (pintype "passive"))
      (node (ref "IC6") (pin "14") (pinfunction "OUT_14") (pintype "output"))
    )
    (net (code "57") (name "Net-(IC7A--IN)") (class "Default")
      (node (ref "FCV3") (pin "1") (pinfunction "1_1") (pintype "passive"))
      (node (ref "IC7") (pin "2") (pinfunction "-IN_2") (pintype "input"))
      (node (ref "R46") (pin "2") (pinfunction "2_2") (pintype "passive"))
      (node (ref "R47") (pin "1") (pinfunction "1_1") (pintype "passive"))
    )
    (net (code "58") (name "Net-(IC7A-OUT)") (class "Default")
      (node (ref "IC7") (pin "1") (pinfunction "OUT_1") (pintype "output"))
      (node (ref "R47") (pin "2") (pinfunction "2_2") (pintype "passive"))
      (node (ref "R48") (pin "1") (pinfunction "1_1") (pintype "passive"))
      (node (ref "R52") (pin "1") (pinfunction "1_1") (pintype "passive"))
    )
    (net (code "59") (name "Net-(IC7B--IN)") (class "Default")
      (node (ref "C33") (pin "1") (pinfunction "1_1") (pintype "passive"))
      (node (ref "D12") (pin "A") (pinfunction "A_A") (pintype "passive"))
      (node (ref "IC7") (pin "6") (pinfunction "-IN_6") (pintype "input"))
      (node (ref "R53") (pin "2") (pinfunction "2_2") (pintype "passive"))
      (node (ref "R54") (pin "2") (pinfunction "2_2") (pintype "passive"))
      (node (ref "R55") (pin "1") (pinfunction "1_1") (pintype "passive"))
    )
    (net (code "60") (name "Net-(IC7B-OUT)") (class "Default")
      (node (ref "C33") (pin "2") (pinfunction "2_2") (pintype "passive"))
      (node (ref "F3") (pin "1") (pinfunction "1_1") (pintype "passive"))
      (node (ref "IC7") (pin "7") (pinfunction "OUT_7") (pintype "output"))
      (node (ref "R55") (pin "2") (pinfunction "2_2") (pintype "passive"))
      (node (ref "R56") (pin "1") (pinfunction "1_1") (pintype "passive"))
    )
    (net (code "61") (name "Net-(IC7C--IN)") (class "Default")
      (node (ref "C32") (pin "1") (pinfunction "1_1") (pintype "passive"))
      (node (ref "IC7") (pin "9") (pinfunction "-IN_9") (pintype "input"))
      (node (ref "R50") (pin "1") (pinfunction "1_1") (pintype "passive"))
      (node (ref "R51") (pin "1") (pinfunction "1_1") (pintype "passive"))
      (node (ref "R52") (pin "2") (pinfunction "2_2") (pintype "passive"))
    )
    (net (code "62") (name "Net-(IC7C-OUT)") (class "Default")
      (node (ref "C32") (pin "2") (pinfunction "2_2") (pintype "passive"))
      (node (ref "IC7") (pin "8") (pinfunction "OUT_8") (pintype "output"))
      (node (ref "R51") (pin "2") (pinfunction "2_2") (pintype "passive"))
      (node (ref "R53") (pin "1") (pinfunction "1_1") (pintype "passive"))
    )
    (net (code "63") (name "Net-(IC7D--IN)") (class "Default")
      (node (ref "D11") (pin "A") (pinfunction "A_A") (pintype "passive"))
      (node (ref "IC7") (pin "13") (pinfunction "-IN_13") (pintype "input"))
      (node (ref "R48") (pin "2") (pinfunction "2_2") (pintype "passive"))
      (node (ref "R49") (pin "1") (pinfunction "1_1") (pintype "passive"))
    )
    (net (code "64") (name "Net-(IC7D-OUT)") (class "Default")
      (node (ref "D11") (pin "C") (pinfunction "C_C") (pintype "passive"))
      (node (ref "D13") (pin "A") (pinfunction "A_A") (pintype "passive"))
      (node (ref "IC7") (pin "14") (pinfunction "OUT_14") (pintype "output"))
    )
    (net (code "65") (name "Net-(JP1-Pad1)") (class "Default")
      (node (ref "JP1") (pin "1") (pinfunction "1_1") (pintype "passive"))
      (node (ref "JP1") (pin "2") (pinfunction "2_2") (pintype "passive"))
      (node (ref "R2") (pin "1") (pinfunction "1_1") (pintype "passive"))
    )
    (net (code "66") (name "Net-(JP1-Pad10)") (class "Default")
      (node (ref "JP1") (pin "10") (pinfunction "10_10") (pintype "passive"))
      (node (ref "JP1") (pin "9") (pinfunction "9_9") (pintype "passive"))
      (node (ref "R1") (pin "1") (pinfunction "1_1") (pintype "passive"))
    )
    (net (code "67") (name "Net-(OFF1-S)") (class "Default")
      (node (ref "OFF1") (pin "2") (pinfunction "S_2") (pintype "passive"))
      (node (ref "R35") (pin "1") (pinfunction "1_1") (pintype "passive"))
    )
    (net (code "68") (name "Net-(OFF2-S)") (class "Default")
      (node (ref "OFF2") (pin "2") (pinfunction "S_2") (pintype "passive"))
      (node (ref "R43") (pin "1") (pinfunction "1_1") (pintype "passive"))
    )
    (net (code "69") (name "Net-(OFF3-S)") (class "Default")
      (node (ref "OFF3") (pin "2") (pinfunction "S_2") (pintype "passive"))
      (node (ref "R54") (pin "1") (pinfunction "1_1") (pintype "passive"))
    )
    (net (code "70") (name "Net-(SAW_OFF-S)") (class "Default")
      (node (ref "R58") (pin "1") (pinfunction "1_1") (pintype "passive"))
      (node (ref "SAW_OFF") (pin "2") (pinfunction "S_2") (pintype "passive"))
    )
    (net (code "71") (name "Net-(SCALE-A)") (class "Default")
      (node (ref "R5") (pin "1") (pinfunction "1_1") (pintype "passive"))
      (node (ref "SCALE") (pin "3") (pinfunction "A_3") (pintype "passive"))
    )
    (net (code "72") (name "Net-(SCALE-E)") (class "Default")
      (node (ref "IC1") (pin "3") (pinfunction "3_3") (pintype "power_in"))
      (node (ref "R3") (pin "2") (pinfunction "2_2") (pintype "passive"))
      (node (ref "R4") (pin "1") (pinfunction "1_1") (pintype "passive"))
      (node (ref "SCALE") (pin "1") (pinfunction "E_1") (pintype "passive"))
      (node (ref "SCALE") (pin "2") (pinfunction "S_2") (pintype "passive"))
    )
    (net (code "73") (name "Net-(TRI_OFF-S)") (class "Default")
      (node (ref "R15") (pin "1") (pinfunction "1_1") (pintype "passive"))
      (node (ref "TRI_OFF") (pin "2") (pinfunction "S_2") (pintype "passive"))
    )
    (net (code "74") (name "V+") (class "Default")
      (node (ref "+V") (pin "1") (pinfunction "1_1") (pintype "passive"))
      (node (ref "C1") (pin "+") (pinfunction "+_+") (pintype "passive"))
      (node (ref "C10") (pin "1") (pinfunction "1_1") (pintype "passive"))
      (node (ref "C11") (pin "1") (pinfunction "1_1") (pintype "passive"))
      (node (ref "C12") (pin "1") (pinfunction "1_1") (pintype "passive"))
      (node (ref "C13") (pin "1") (pinfunction "1_1") (pintype "passive"))
      (node (ref "C16") (pin "2") (pinfunction "2_2") (pintype "passive"))
      (node (ref "C18") (pin "2") (pinfunction "2_2") (pintype "passive"))
      (node (ref "C20") (pin "1") (pinfunction "1_1") (pintype "passive"))
      (node (ref "C21") (pin "1") (pinfunction "1_1") (pintype "passive"))
      (node (ref "C6") (pin "1") (pinfunction "1_1") (pintype "passive"))
      (node (ref "C9") (pin "1") (pinfunction "1_1") (pintype "passive"))
      (node (ref "C_TUNE") (pin "3") (pinfunction "A_3") (pintype "passive"))
      (node (ref "IC1") (pin "16") (pinfunction "16_16") (pintype "power_in"))
      (node (ref "OFF1") (pin "3") (pinfunction "A_3") (pintype "passive"))
      (node (ref "OFF2") (pin "3") (pinfunction "A_3") (pintype "passive"))
      (node (ref "OFF3") (pin "3") (pinfunction "A_3") (pintype "passive"))
      (node (ref "R1") (pin "2") (pinfunction "2_2") (pintype "passive"))
      (node (ref "R10") (pin "2") (pinfunction "2_2") (pintype "passive"))
      (node (ref "SAW_OFF") (pin "3") (pinfunction "A_3") (pintype "passive"))
      (node (ref "TRI_OFF") (pin "3") (pinfunction "A_3") (pintype "passive"))
    )
    (net (code "75") (name "V-") (class "Default")
      (node (ref "-V") (pin "1") (pinfunction "1_1") (pintype "passive"))
      (node (ref "C14") (pin "2") (pinfunction "2_2") (pintype "passive"))
      (node (ref "C15") (pin "2") (pinfunction "2_2") (pintype "passive"))
      (node (ref "C17") (pin "2") (pinfunction "2_2") (pintype "passive"))
      (node (ref "C19") (pin "2") (pinfunction "2_2") (pintype "passive"))
      (node (ref "C2") (pin "-") (pinfunction "-_-") (pintype "passive"))
      (node (ref "C22") (pin "2") (pinfunction "2_2") (pintype "passive"))
      (node (ref "C23") (pin "2") (pinfunction "2_2") (pintype "passive"))
      (node (ref "C25") (pin "2") (pinfunction "2_2") (pintype "passive"))
      (node (ref "C26") (pin "2") (pinfunction "2_2") (pintype "passive"))
      (node (ref "C27") (pin "2") (pinfunction "2_2") (pintype "passive"))
      (node (ref "C_TUNE") (pin "1") (pinfunction "E_1") (pintype "passive"))
      (node (ref "OFF1") (pin "1") (pinfunction "E_1") (pintype "passive"))
      (node (ref "OFF2") (pin "1") (pinfunction "E_1") (pintype "passive"))
      (node (ref "OFF3") (pin "1") (pinfunction "E_1") (pintype "passive"))
      (node (ref "R2") (pin "2") (pinfunction "2_2") (pintype "passive"))
      (node (ref "R3") (pin "1") (pinfunction "1_1") (pintype "passive"))
    )
    (net (code "76") (name "unconnected-(IC1-Pad4)") (class "Default")
      (node (ref "IC1") (pin "4") (pinfunction "4_4") (pintype "output"))
    )
    (net (code "77") (name "unconnected-(IC1-Pad5)") (class "Default")
      (node (ref "IC1") (pin "5") (pinfunction "5_5") (pintype "input"))
    )
  )
)
